# Camera_IR.net
KiCad netlist of a schematic drawn in EasyEDA
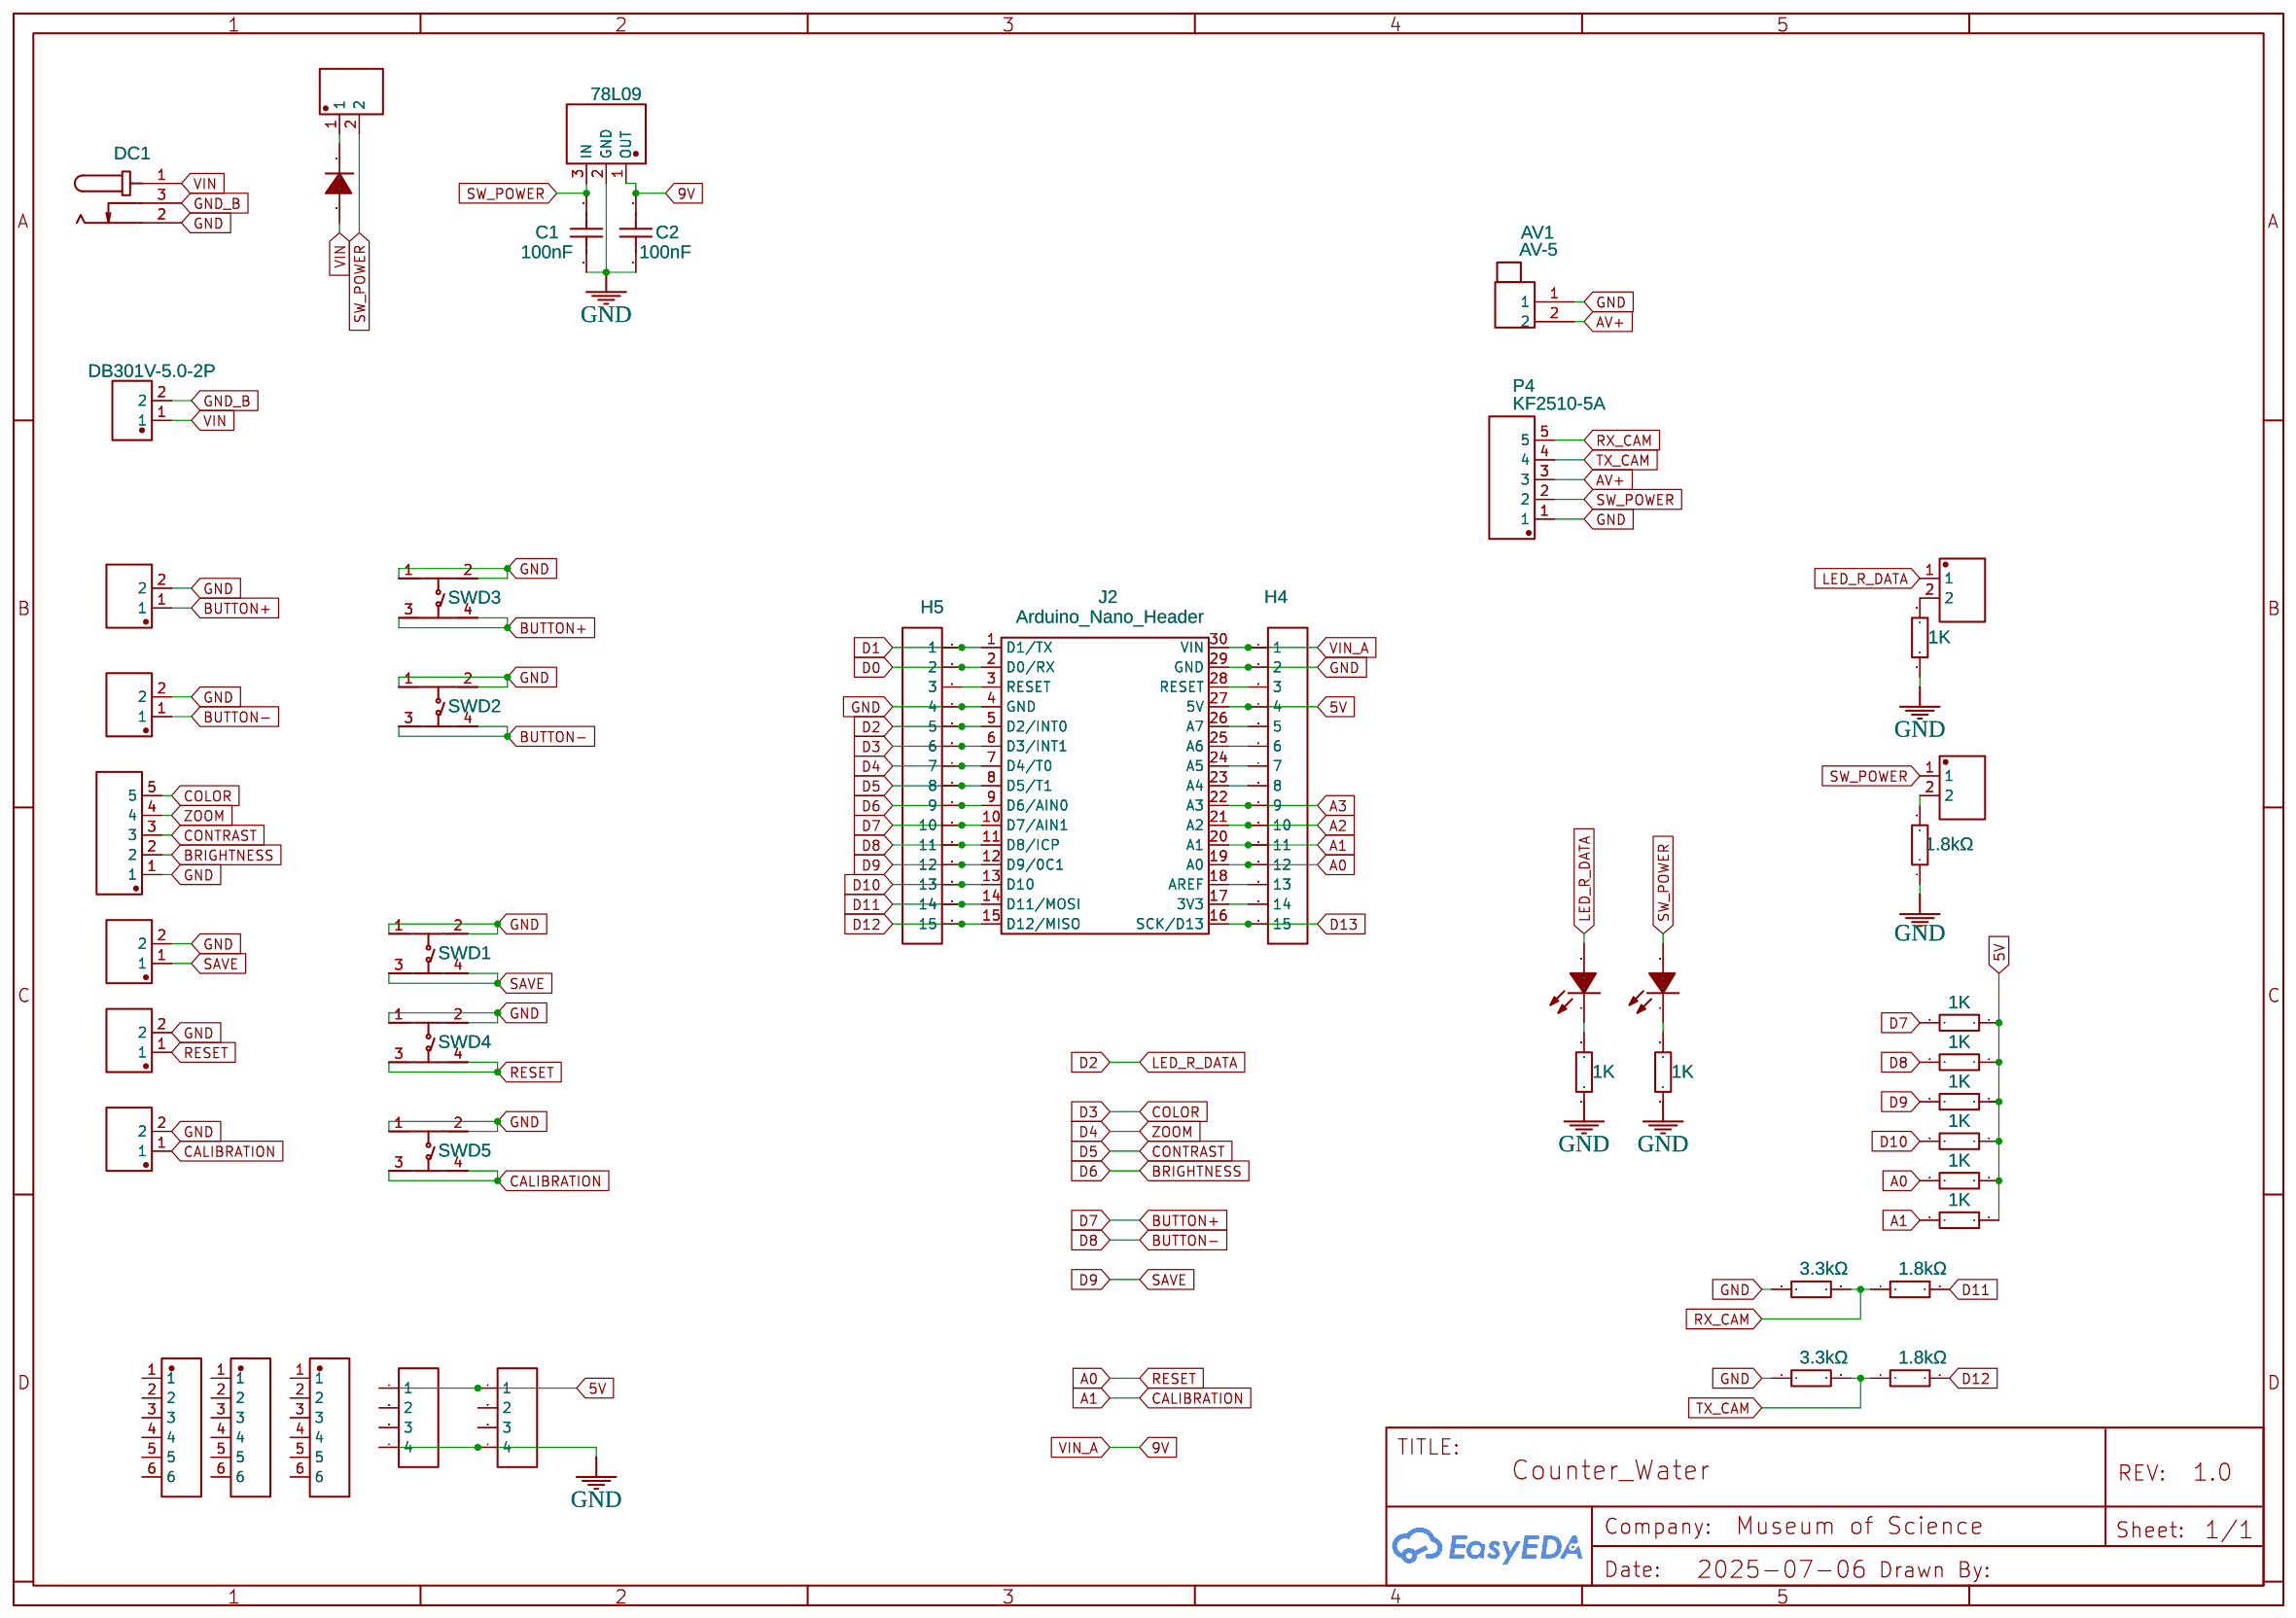
[diagram p0: schematic sheet]

(export (version "E")
  (design (tool "Eeschema 10.0.6"))
  (components
    (comp (ref "A0")
      (value "RESET")
      (fields (field (name "Manufacturer Part") "KF2510-2A") (field (name "Manufacturer") "BOOMELE"))
      (libsource (lib "") (part "KF2510-2A_3"))
    )
    (comp (ref "A1")
      (value "FFC")
      (fields (field (name "Manufacturer Part") "KF2510-2A") (field (name "Manufacturer") "BOOMELE"))
      (libsource (lib "") (part "KF2510-2A_3"))
    )
    (comp (ref "AV1")
      (value "AV-5")
      (fields (field (name "Manufacturer") "BOOMELE(博穆精密)"))
      (libsource (lib "") (part "AV-5"))
    )
    (comp (ref "C1")
      (value "100nF")
      (fields
        (field (name "Manufacturer Part") "CC0603KRX7R9BB104")
        (field (name "Manufacturer") "YAGEO(国巨)")
      )
      (libsource (lib "") (part "CC0603KRX7R9BB104"))
    )
    (comp (ref "C2")
      (value "100nF")
      (fields
        (field (name "Manufacturer Part") "CC0603KRX7R9BB104")
        (field (name "Manufacturer") "YAGEO(国巨)")
      )
      (libsource (lib "") (part "CC0603KRX7R9BB104"))
    )
    (comp (ref "D2")
      (value "LED")
      (fields (field (name "Manufacturer Part") "KF2510-2A") (field (name "Manufacturer") "BOOMELE"))
      (libsource (lib "") (part "KF2510-2A_4"))
    )
    (comp (ref "D7")
      (value "B+")
      (fields (field (name "Manufacturer Part") "KF2510-2A") (field (name "Manufacturer") "BOOMELE"))
      (libsource (lib "") (part "KF2510-2A_1"))
    )
    (comp (ref "D8")
      (value "B-")
      (fields (field (name "Manufacturer Part") "KF2510-2A") (field (name "Manufacturer") "BOOMELE"))
      (libsource (lib "") (part "KF2510-2A_1"))
    )
    (comp (ref "D9")
      (value "SAVE")
      (fields (field (name "Manufacturer Part") "KF2510-2A") (field (name "Manufacturer") "BOOMELE"))
      (libsource (lib "") (part "KF2510-2A_1"))
    )
    (comp (ref "DC1")
      (value "DC")
      (fields (field (name "Manufacturer Part") "DC005-2.0MM") (field (name "Manufacturer") "SOFNG"))
      (libsource (lib "") (part "DC005-2.0MM"))
    )
    (comp (ref "DDM2")
      (value "1N4007")
      (fields (field (name "Manufacturer Part") "1N4007F") (field (name "Manufacturer") "SK"))
      (libsource (lib "") (part "1N4007F"))
    )
    (comp (ref "ERL1")
      (value "1K")
      (fields (field (name "Manufacturer Part") "0603WAF1001T5E") (field (name "Manufacturer") "UniOhm"))
      (libsource (lib "") (part "0603WAF1001T5E"))
    )
    (comp (ref "ERL2")
      (value "1K")
      (fields (field (name "Manufacturer Part") "0603WAF1001T5E") (field (name "Manufacturer") "UniOhm"))
      (libsource (lib "") (part "0603WAF1001T5E_1"))
    )
    (comp (ref "ERL3")
      (value "1K")
      (fields (field (name "Manufacturer Part") "0603WAF1001T5E") (field (name "Manufacturer") "UniOhm"))
      (libsource (lib "") (part "0603WAF1001T5E_1"))
    )
    (comp (ref "ERL4")
      (value "1K")
      (fields (field (name "Manufacturer Part") "0603WAF1001T5E") (field (name "Manufacturer") "UniOhm"))
      (libsource (lib "") (part "0603WAF1001T5E"))
    )
    (comp (ref "ERL5")
      (value "1K")
      (fields (field (name "Manufacturer Part") "0603WAF1001T5E") (field (name "Manufacturer") "UniOhm"))
      (libsource (lib "") (part "0603WAF1001T5E"))
    )
    (comp (ref "ERL6")
      (value "1K")
      (fields (field (name "Manufacturer Part") "0603WAF1001T5E") (field (name "Manufacturer") "UniOhm"))
      (libsource (lib "") (part "0603WAF1001T5E_1"))
    )
    (comp (ref "ERL9")
      (value "1K")
      (fields (field (name "Manufacturer Part") "0603WAF1001T5E") (field (name "Manufacturer") "UniOhm"))
      (libsource (lib "") (part "0603WAF1001T5E_1"))
    )
    (comp (ref "ERL11")
      (value "1K")
      (fields (field (name "Manufacturer Part") "0603WAF1001T5E") (field (name "Manufacturer") "UniOhm"))
      (libsource (lib "") (part "0603WAF1001T5E_1"))
    )
    (comp (ref "ERL12")
      (value "1K")
      (fields (field (name "Manufacturer Part") "0603WAF1001T5E") (field (name "Manufacturer") "UniOhm"))
      (libsource (lib "") (part "0603WAF1001T5E_1"))
    )
    (comp (ref "H4") (value "HDR-F-2.54_1x15") (libsource (lib "") (part "HDR-F-2.54_1x15")))
    (comp (ref "H5") (value "HDR-F-2.54_1x15") (libsource (lib "") (part "HDR-F-2.54_1x15_1")))
    (comp (ref "J2") (value "Arduino_Nano_Header") (libsource (lib "") (part "Arduino_Nano_Header")))
    (comp (ref "J6") (value "HDR-M-2.54_1x4") (libsource (lib "") (part "HDR-M-2.54_1x4")))
    (comp (ref "J7") (value "HDR-M-2.54_1x4") (libsource (lib "") (part "HDR-M-2.54_1x4")))
    (comp (ref "LED4")
      (value "KT-0603R")
      (fields (field (name "Manufacturer") "KENTO"))
      (libsource (lib "") (part "KT-0603R"))
    )
    (comp (ref "LED5")
      (value "KT-0603R")
      (fields (field (name "Manufacturer") "KENTO"))
      (libsource (lib "") (part "KT-0603R"))
    )
    (comp (ref "LED_P")
      (value "LED_POWER")
      (fields (field (name "Manufacturer Part") "KF2510-2A") (field (name "Manufacturer") "BOOMELE"))
      (libsource (lib "") (part "KF2510-2A_2"))
    )
    (comp (ref "P1")
      (value "KF2510-5A")
      (fields (field (name "Manufacturer Part") "2510-5A") (field (name "Manufacturer") "BOOMELE(博穆精密)"))
      (libsource (lib "") (part "KF2510-5A"))
    )
    (comp (ref "P2")
      (value "H6")
      (fields (field (name "Manufacturer Part") "2.54-1*6P母") (field (name "Manufacturer") "BOOMELE(博穆精密)"))
      (libsource (lib "") (part "Header-Female-2.54_1x6"))
    )
    (comp (ref "P3")
      (value "H6")
      (fields (field (name "Manufacturer Part") "2.54-1*6P母") (field (name "Manufacturer") "BOOMELE(博穆精密)"))
      (libsource (lib "") (part "Header-Female-2.54_1x6"))
    )
    (comp (ref "P4")
      (value "KF2510-5A")
      (fields (field (name "Manufacturer Part") "2510-5A") (field (name "Manufacturer") "BOOMELE(博穆精密)"))
      (libsource (lib "") (part "KF2510-5A"))
    )
    (comp (ref "P5")
      (value "H6")
      (fields (field (name "Manufacturer Part") "2.54-1*6P母") (field (name "Manufacturer") "BOOMELE(博穆精密)"))
      (libsource (lib "") (part "Header-Female-2.54_1x6"))
    )
    (comp (ref "R1")
      (value "1.8kΩ")
      (fields
        (field (name "Manufacturer Part") "0603WAF1801T5E")
        (field (name "Manufacturer") "UNI-ROYAL(厚声)")
      )
      (libsource (lib "") (part "0603WAF1801T5E"))
    )
    (comp (ref "R2")
      (value "1.8kΩ")
      (fields
        (field (name "Manufacturer Part") "0603WAF1801T5E")
        (field (name "Manufacturer") "UNI-ROYAL(厚声)")
      )
      (libsource (lib "") (part "0603WAF1801T5E"))
    )
    (comp (ref "R3")
      (value "3.3kΩ")
      (fields
        (field (name "Manufacturer Part") "0402WGF3301TCE")
        (field (name "Manufacturer") "UNI-ROYAL(厚声)")
      )
      (libsource (lib "") (part "0402WGF3301TCE"))
    )
    (comp (ref "R4")
      (value "3.3kΩ")
      (fields
        (field (name "Manufacturer Part") "0402WGF3301TCE")
        (field (name "Manufacturer") "UNI-ROYAL(厚声)")
      )
      (libsource (lib "") (part "0402WGF3301TCE"))
    )
    (comp (ref "R5")
      (value "1.8kΩ")
      (fields
        (field (name "Manufacturer Part") "0603WAF1801T5E")
        (field (name "Manufacturer") "UNI-ROYAL(厚声)")
      )
      (libsource (lib "") (part "0603WAF1801T5E_1"))
    )
    (comp (ref "SWD1")
      (value "TC-6610-7-160G")
      (fields (field (name "Manufacturer") "HCTL(华灿天禄)"))
      (libsource (lib "") (part "TC-6610-7-160G"))
    )
    (comp (ref "SWD2")
      (value "TC-6610-7-160G")
      (fields (field (name "Manufacturer") "HCTL(华灿天禄)"))
      (libsource (lib "") (part "TC-6610-7-160G"))
    )
    (comp (ref "SWD3")
      (value "TC-6610-7-160G")
      (fields (field (name "Manufacturer") "HCTL(华灿天禄)"))
      (libsource (lib "") (part "TC-6610-7-160G"))
    )
    (comp (ref "SWD4")
      (value "TC-6610-7-160G")
      (fields (field (name "Manufacturer") "HCTL(华灿天禄)"))
      (libsource (lib "") (part "TC-6610-7-160G"))
    )
    (comp (ref "SWD5")
      (value "TC-6610-7-160G")
      (fields (field (name "Manufacturer") "HCTL(华灿天禄)"))
      (libsource (lib "") (part "TC-6610-7-160G"))
    )
    (comp (ref "SW_P")
      (value "SW_P")
      (fields (field (name "Manufacturer Part") "KF2510-2A") (field (name "Manufacturer") "BOOMELE"))
      (libsource (lib "") (part "KF2510-2A"))
    )
    (comp (ref "U1")
      (value "78L09")
      (fields (field (name "Manufacturer") "CBI(创基)"))
      (libsource (lib "") (part "78L09U 78L09"))
    )
    (comp (ref "U3")
      (value "DB301V-5.0-2P")
      (fields
        (field (name "Manufacturer Part") "DB301V-5.0-2P-BU-S")
        (field (name "Manufacturer") "DORABO(地博电气)")
      )
      (libsource (lib "") (part "DB301V-5.0-2P"))
    )
  )
  (nets
    (net (code "1") (name "5V") (class "Default")
      (node (ref "ERL11") (pin "1") (pinfunction "1_1") (pintype "input"))
      (node (ref "ERL12") (pin "1") (pinfunction "1_1") (pintype "input"))
      (node (ref "ERL2") (pin "1") (pinfunction "1_1") (pintype "input"))
      (node (ref "ERL3") (pin "1") (pinfunction "1_1") (pintype "input"))
      (node (ref "ERL6") (pin "1") (pinfunction "1_1") (pintype "input"))
      (node (ref "ERL9") (pin "1") (pinfunction "1_1") (pintype "input"))
      (node (ref "H4") (pin "4") (pinfunction "4_4") (pintype "unspecified"))
      (node (ref "J2") (pin "27") (pinfunction "5V_27") (pintype "unspecified"))
      (node (ref "J6") (pin "1") (pinfunction "1_1") (pintype "unspecified"))
      (node (ref "J7") (pin "1") (pinfunction "1_1") (pintype "unspecified"))
    )
    (net (code "2") (name "9V") (class "Default")
      (node (ref "C2") (pin "2") (pinfunction "2_2") (pintype "unspecified"))
      (node (ref "H4") (pin "1") (pinfunction "1_1") (pintype "unspecified"))
      (node (ref "J2") (pin "30") (pinfunction "VIN_30") (pintype "unspecified"))
      (node (ref "U1") (pin "1") (pinfunction "OUT_1") (pintype "unspecified"))
    )
    (net (code "3") (name "A0") (class "Default")
      (node (ref "A0") (pin "1") (pinfunction "1_1") (pintype "unspecified"))
      (node (ref "ERL2") (pin "2") (pinfunction "2_2") (pintype "input"))
      (node (ref "H4") (pin "12") (pinfunction "12_12") (pintype "unspecified"))
      (node (ref "J2") (pin "19") (pinfunction "A0_19") (pintype "unspecified"))
      (node (ref "SWD4") (pin "3") (pinfunction "3_3") (pintype "unspecified"))
      (node (ref "SWD4") (pin "4") (pinfunction "4_4") (pintype "unspecified"))
    )
    (net (code "4") (name "A1") (class "Default")
      (node (ref "A1") (pin "1") (pinfunction "1_1") (pintype "unspecified"))
      (node (ref "ERL3") (pin "2") (pinfunction "2_2") (pintype "input"))
      (node (ref "H4") (pin "11") (pinfunction "11_11") (pintype "unspecified"))
      (node (ref "J2") (pin "20") (pinfunction "A1_20") (pintype "unspecified"))
      (node (ref "SWD5") (pin "3") (pinfunction "3_3") (pintype "unspecified"))
      (node (ref "SWD5") (pin "4") (pinfunction "4_4") (pintype "unspecified"))
    )
    (net (code "5") (name "A2") (class "Default")
      (node (ref "H4") (pin "10") (pinfunction "10_10") (pintype "unspecified"))
      (node (ref "J2") (pin "21") (pinfunction "A2_21") (pintype "unspecified"))
    )
    (net (code "6") (name "A3") (class "Default")
      (node (ref "H4") (pin "9") (pinfunction "9_9") (pintype "unspecified"))
      (node (ref "J2") (pin "22") (pinfunction "A3_22") (pintype "unspecified"))
    )
    (net (code "7") (name "AV+") (class "Default")
      (node (ref "AV1") (pin "2") (pinfunction "2_2") (pintype "unspecified"))
      (node (ref "P4") (pin "3") (pinfunction "3_3") (pintype "unspecified"))
    )
    (net (code "8") (name "BRIGHTNESS") (class "Default")
      (node (ref "H5") (pin "9") (pinfunction "9_9") (pintype "unspecified"))
      (node (ref "J2") (pin "9") (pinfunction "D6/AIN0_9") (pintype "unspecified"))
      (node (ref "P1") (pin "2") (pinfunction "2_2") (pintype "unspecified"))
    )
    (net (code "9") (name "BUTTON+") (class "Default")
      (node (ref "D7") (pin "1") (pinfunction "1_1") (pintype "unspecified"))
      (node (ref "ERL6") (pin "2") (pinfunction "2_2") (pintype "input"))
      (node (ref "H5") (pin "10") (pinfunction "10_10") (pintype "unspecified"))
      (node (ref "J2") (pin "10") (pinfunction "D7/AIN1_10") (pintype "unspecified"))
      (node (ref "SWD3") (pin "3") (pinfunction "3_3") (pintype "unspecified"))
      (node (ref "SWD3") (pin "4") (pinfunction "4_4") (pintype "unspecified"))
    )
    (net (code "10") (name "BUTTON-") (class "Default")
      (node (ref "D8") (pin "1") (pinfunction "1_1") (pintype "unspecified"))
      (node (ref "ERL11") (pin "2") (pinfunction "2_2") (pintype "input"))
      (node (ref "H5") (pin "11") (pinfunction "11_11") (pintype "unspecified"))
      (node (ref "J2") (pin "11") (pinfunction "D8/ICP_11") (pintype "unspecified"))
      (node (ref "SWD2") (pin "3") (pinfunction "3_3") (pintype "unspecified"))
      (node (ref "SWD2") (pin "4") (pinfunction "4_4") (pintype "unspecified"))
    )
    (net (code "11") (name "COLOR") (class "Default")
      (node (ref "H5") (pin "6") (pinfunction "6_6") (pintype "unspecified"))
      (node (ref "J2") (pin "6") (pinfunction "D3/INT1_6") (pintype "unspecified"))
      (node (ref "P1") (pin "5") (pinfunction "5_5") (pintype "unspecified"))
    )
    (net (code "12") (name "CONTRAST") (class "Default")
      (node (ref "H5") (pin "8") (pinfunction "8_8") (pintype "unspecified"))
      (node (ref "J2") (pin "8") (pinfunction "D5/T1_8") (pintype "unspecified"))
      (node (ref "P1") (pin "3") (pinfunction "3_3") (pintype "unspecified"))
    )
    (net (code "13") (name "D0") (class "Default")
      (node (ref "H5") (pin "2") (pinfunction "2_2") (pintype "unspecified"))
      (node (ref "J2") (pin "2") (pinfunction "D0/RX_2") (pintype "unspecified"))
    )
    (net (code "14") (name "D1") (class "Default")
      (node (ref "H5") (pin "1") (pinfunction "1_1") (pintype "unspecified"))
      (node (ref "J2") (pin "1") (pinfunction "D1/TX_1") (pintype "unspecified"))
    )
    (net (code "15") (name "D2") (class "Default")
      (node (ref "D2") (pin "1") (pinfunction "1_1") (pintype "unspecified"))
      (node (ref "H5") (pin "5") (pinfunction "5_5") (pintype "unspecified"))
      (node (ref "J2") (pin "5") (pinfunction "D2/INT0_5") (pintype "unspecified"))
      (node (ref "LED5") (pin "2") (pinfunction "A_2") (pintype "unspecified"))
    )
    (net (code "16") (name "D4") (class "Default")
      (node (ref "H5") (pin "7") (pinfunction "7_7") (pintype "unspecified"))
      (node (ref "J2") (pin "7") (pinfunction "D4/T0_7") (pintype "unspecified"))
      (node (ref "P1") (pin "4") (pinfunction "4_4") (pintype "unspecified"))
    )
    (net (code "17") (name "D9") (class "Default")
      (node (ref "D9") (pin "1") (pinfunction "1_1") (pintype "unspecified"))
      (node (ref "ERL9") (pin "2") (pinfunction "2_2") (pintype "input"))
      (node (ref "H5") (pin "12") (pinfunction "12_12") (pintype "unspecified"))
      (node (ref "J2") (pin "12") (pinfunction "D9/0C1_12") (pintype "unspecified"))
      (node (ref "SWD1") (pin "3") (pinfunction "3_3") (pintype "unspecified"))
      (node (ref "SWD1") (pin "4") (pinfunction "4_4") (pintype "unspecified"))
    )
    (net (code "18") (name "D10") (class "Default")
      (node (ref "ERL12") (pin "2") (pinfunction "2_2") (pintype "input"))
      (node (ref "H5") (pin "13") (pinfunction "13_13") (pintype "unspecified"))
      (node (ref "J2") (pin "13") (pinfunction "D10_13") (pintype "unspecified"))
    )
    (net (code "19") (name "D11") (class "Default")
      (node (ref "H5") (pin "14") (pinfunction "14_14") (pintype "unspecified"))
      (node (ref "J2") (pin "14") (pinfunction "D11/MOSI_14") (pintype "unspecified"))
      (node (ref "R1") (pin "2") (pinfunction "2_2") (pintype "input"))
    )
    (net (code "20") (name "D12") (class "Default")
      (node (ref "H5") (pin "15") (pinfunction "15_15") (pintype "unspecified"))
      (node (ref "J2") (pin "15") (pinfunction "D12/MISO_15") (pintype "unspecified"))
      (node (ref "R2") (pin "2") (pinfunction "2_2") (pintype "input"))
    )
    (net (code "21") (name "D13") (class "Default")
      (node (ref "H4") (pin "15") (pinfunction "15_15") (pintype "unspecified"))
      (node (ref "J2") (pin "16") (pinfunction "SCK/D13_16") (pintype "unspecified"))
    )
    (net (code "22") (name "GND") (class "Default")
      (node (ref "A0") (pin "2") (pinfunction "2_2") (pintype "unspecified"))
      (node (ref "A1") (pin "2") (pinfunction "2_2") (pintype "unspecified"))
      (node (ref "AV1") (pin "1") (pinfunction "1_1") (pintype "unspecified"))
      (node (ref "C1") (pin "1") (pinfunction "1_1") (pintype "unspecified"))
      (node (ref "C2") (pin "1") (pinfunction "1_1") (pintype "unspecified"))
      (node (ref "D7") (pin "2") (pinfunction "2_2") (pintype "unspecified"))
      (node (ref "D8") (pin "2") (pinfunction "2_2") (pintype "unspecified"))
      (node (ref "D9") (pin "2") (pinfunction "2_2") (pintype "unspecified"))
      (node (ref "DC1") (pin "2") (pinfunction "2_2") (pintype "unspecified"))
      (node (ref "ERL1") (pin "1") (pinfunction "1_1") (pintype "input"))
      (node (ref "ERL4") (pin "1") (pinfunction "1_1") (pintype "input"))
      (node (ref "ERL5") (pin "1") (pinfunction "1_1") (pintype "input"))
      (node (ref "H4") (pin "2") (pinfunction "2_2") (pintype "unspecified"))
      (node (ref "H5") (pin "4") (pinfunction "4_4") (pintype "unspecified"))
      (node (ref "J2") (pin "29") (pinfunction "GND_29") (pintype "unspecified"))
      (node (ref "J2") (pin "4") (pinfunction "GND_4") (pintype "unspecified"))
      (node (ref "J6") (pin "4") (pinfunction "4_4") (pintype "unspecified"))
      (node (ref "J7") (pin "4") (pinfunction "4_4") (pintype "unspecified"))
      (node (ref "P1") (pin "1") (pinfunction "1_1") (pintype "unspecified"))
      (node (ref "P4") (pin "1") (pinfunction "1_1") (pintype "unspecified"))
      (node (ref "R3") (pin "1") (pinfunction "1_1") (pintype "input"))
      (node (ref "R4") (pin "1") (pinfunction "1_1") (pintype "input"))
      (node (ref "R5") (pin "1") (pinfunction "1_1") (pintype "input"))
      (node (ref "SWD1") (pin "1") (pinfunction "1_1") (pintype "unspecified"))
      (node (ref "SWD1") (pin "2") (pinfunction "2_2") (pintype "unspecified"))
      (node (ref "SWD2") (pin "1") (pinfunction "1_1") (pintype "unspecified"))
      (node (ref "SWD2") (pin "2") (pinfunction "2_2") (pintype "unspecified"))
      (node (ref "SWD3") (pin "1") (pinfunction "1_1") (pintype "unspecified"))
      (node (ref "SWD3") (pin "2") (pinfunction "2_2") (pintype "unspecified"))
      (node (ref "SWD4") (pin "1") (pinfunction "1_1") (pintype "unspecified"))
      (node (ref "SWD4") (pin "2") (pinfunction "2_2") (pintype "unspecified"))
      (node (ref "SWD5") (pin "1") (pinfunction "1_1") (pintype "unspecified"))
      (node (ref "SWD5") (pin "2") (pinfunction "2_2") (pintype "unspecified"))
      (node (ref "U1") (pin "2") (pinfunction "GND_2") (pintype "unspecified"))
    )
    (net (code "23") (name "GND_B") (class "Default")
      (node (ref "DC1") (pin "3") (pinfunction "3_3") (pintype "unspecified"))
      (node (ref "U3") (pin "2") (pinfunction "2_2") (pintype "unspecified"))
    )
    (net (code "24") (name "Net-(D2-Pad2)") (class "Default")
      (node (ref "D2") (pin "2") (pinfunction "2_2") (pintype "unspecified"))
      (node (ref "ERL5") (pin "2") (pinfunction "2_2") (pintype "input"))
    )
    (net (code "25") (name "Net-(DDM2-C)") (class "Default")
      (node (ref "DDM2") (pin "1") (pinfunction "C_1") (pintype "unspecified"))
      (node (ref "SW_P") (pin "1") (pinfunction "1_1") (pintype "unspecified"))
    )
    (net (code "26") (name "Net-(H4-Pad3)") (class "Default")
      (node (ref "H4") (pin "3") (pinfunction "3_3") (pintype "unspecified"))
      (node (ref "J2") (pin "28") (pinfunction "RESET_28") (pintype "unspecified"))
    )
    (net (code "27") (name "Net-(H5-Pad3)") (class "Default")
      (node (ref "H5") (pin "3") (pinfunction "3_3") (pintype "unspecified"))
      (node (ref "J2") (pin "3") (pinfunction "RESET_3") (pintype "unspecified"))
    )
    (net (code "28") (name "Net-(J2-3V3)") (class "Default")
      (node (ref "H4") (pin "14") (pinfunction "14_14") (pintype "unspecified"))
      (node (ref "J2") (pin "17") (pinfunction "3V3_17") (pintype "unspecified"))
    )
    (net (code "29") (name "Net-(J2-A4)") (class "Default")
      (node (ref "H4") (pin "8") (pinfunction "8_8") (pintype "unspecified"))
      (node (ref "J2") (pin "23") (pinfunction "A4_23") (pintype "unspecified"))
    )
    (net (code "30") (name "Net-(J2-A5)") (class "Default")
      (node (ref "H4") (pin "7") (pinfunction "7_7") (pintype "unspecified"))
      (node (ref "J2") (pin "24") (pinfunction "A5_24") (pintype "unspecified"))
    )
    (net (code "31") (name "Net-(J2-A6)") (class "Default")
      (node (ref "H4") (pin "6") (pinfunction "6_6") (pintype "unspecified"))
      (node (ref "J2") (pin "25") (pinfunction "A6_25") (pintype "unspecified"))
    )
    (net (code "32") (name "Net-(J2-A7)") (class "Default")
      (node (ref "H4") (pin "5") (pinfunction "5_5") (pintype "unspecified"))
      (node (ref "J2") (pin "26") (pinfunction "A7_26") (pintype "unspecified"))
    )
    (net (code "33") (name "Net-(J2-AREF)") (class "Default")
      (node (ref "H4") (pin "13") (pinfunction "13_13") (pintype "unspecified"))
      (node (ref "J2") (pin "18") (pinfunction "AREF_18") (pintype "unspecified"))
    )
    (net (code "34") (name "Net-(LED4-K)") (class "Default")
      (node (ref "ERL4") (pin "2") (pinfunction "2_2") (pintype "input"))
      (node (ref "LED4") (pin "1") (pinfunction "K_1") (pintype "unspecified"))
    )
    (net (code "35") (name "Net-(LED5-K)") (class "Default")
      (node (ref "ERL1") (pin "2") (pinfunction "2_2") (pintype "input"))
      (node (ref "LED5") (pin "1") (pinfunction "K_1") (pintype "unspecified"))
    )
    (net (code "36") (name "Net-(LED_P-Pad2)") (class "Default")
      (node (ref "LED_P") (pin "2") (pinfunction "2_2") (pintype "unspecified"))
      (node (ref "R5") (pin "2") (pinfunction "2_2") (pintype "input"))
    )
    (net (code "37") (name "RX_CAM") (class "Default")
      (node (ref "P4") (pin "5") (pinfunction "5_5") (pintype "unspecified"))
      (node (ref "R1") (pin "1") (pinfunction "1_1") (pintype "input"))
      (node (ref "R3") (pin "2") (pinfunction "2_2") (pintype "input"))
    )
    (net (code "38") (name "SW_POWER") (class "Default")
      (node (ref "C1") (pin "2") (pinfunction "2_2") (pintype "unspecified"))
      (node (ref "LED4") (pin "2") (pinfunction "A_2") (pintype "unspecified"))
      (node (ref "LED_P") (pin "1") (pinfunction "1_1") (pintype "unspecified"))
      (node (ref "P4") (pin "2") (pinfunction "2_2") (pintype "unspecified"))
      (node (ref "SW_P") (pin "2") (pinfunction "2_2") (pintype "unspecified"))
      (node (ref "U1") (pin "3") (pinfunction "IN_3") (pintype "unspecified"))
    )
    (net (code "39") (name "TX_CAM") (class "Default")
      (node (ref "P4") (pin "4") (pinfunction "4_4") (pintype "unspecified"))
      (node (ref "R2") (pin "1") (pinfunction "1_1") (pintype "input"))
      (node (ref "R4") (pin "2") (pinfunction "2_2") (pintype "input"))
    )
    (net (code "40") (name "VIN") (class "Default")
      (node (ref "DC1") (pin "1") (pinfunction "1_1") (pintype "unspecified"))
      (node (ref "DDM2") (pin "2") (pinfunction "A_2") (pintype "unspecified"))
      (node (ref "U3") (pin "1") (pinfunction "1_1") (pintype "unspecified"))
    )
    (net (code "41") (name "unconnected-(J6-Pad2)") (class "Default")
      (node (ref "J6") (pin "2") (pinfunction "2_2") (pintype "unspecified"))
    )
    (net (code "42") (name "unconnected-(J6-Pad3)") (class "Default")
      (node (ref "J6") (pin "3") (pinfunction "3_3") (pintype "unspecified"))
    )
    (net (code "43") (name "unconnected-(J7-Pad2)") (class "Default")
      (node (ref "J7") (pin "2") (pinfunction "2_2") (pintype "unspecified"))
    )
    (net (code "44") (name "unconnected-(J7-Pad3)") (class "Default")
      (node (ref "J7") (pin "3") (pinfunction "3_3") (pintype "unspecified"))
    )
    (net (code "45") (name "unconnected-(P2-Pad1)") (class "Default")
      (node (ref "P2") (pin "1") (pinfunction "1_1") (pintype "unspecified"))
    )
    (net (code "46") (name "unconnected-(P2-Pad2)") (class "Default")
      (node (ref "P2") (pin "2") (pinfunction "2_2") (pintype "unspecified"))
    )
    (net (code "47") (name "unconnected-(P2-Pad3)") (class "Default")
      (node (ref "P2") (pin "3") (pinfunction "3_3") (pintype "unspecified"))
    )
    (net (code "48") (name "unconnected-(P2-Pad4)") (class "Default")
      (node (ref "P2") (pin "4") (pinfunction "4_4") (pintype "unspecified"))
    )
    (net (code "49") (name "unconnected-(P2-Pad5)") (class "Default")
      (node (ref "P2") (pin "5") (pinfunction "5_5") (pintype "unspecified"))
    )
    (net (code "50") (name "unconnected-(P2-Pad6)") (class "Default")
      (node (ref "P2") (pin "6") (pinfunction "6_6") (pintype "unspecified"))
    )
    (net (code "51") (name "unconnected-(P3-Pad1)") (class "Default")
      (node (ref "P3") (pin "1") (pinfunction "1_1") (pintype "unspecified"))
    )
    (net (code "52") (name "unconnected-(P3-Pad2)") (class "Default")
      (node (ref "P3") (pin "2") (pinfunction "2_2") (pintype "unspecified"))
    )
    (net (code "53") (name "unconnected-(P3-Pad3)") (class "Default")
      (node (ref "P3") (pin "3") (pinfunction "3_3") (pintype "unspecified"))
    )
    (net (code "54") (name "unconnected-(P3-Pad4)") (class "Default")
      (node (ref "P3") (pin "4") (pinfunction "4_4") (pintype "unspecified"))
    )
    (net (code "55") (name "unconnected-(P3-Pad5)") (class "Default")
      (node (ref "P3") (pin "5") (pinfunction "5_5") (pintype "unspecified"))
    )
    (net (code "56") (name "unconnected-(P3-Pad6)") (class "Default")
      (node (ref "P3") (pin "6") (pinfunction "6_6") (pintype "unspecified"))
    )
    (net (code "57") (name "unconnected-(P5-Pad1)") (class "Default")
      (node (ref "P5") (pin "1") (pinfunction "1_1") (pintype "unspecified"))
    )
    (net (code "58") (name "unconnected-(P5-Pad2)") (class "Default")
      (node (ref "P5") (pin "2") (pinfunction "2_2") (pintype "unspecified"))
    )
    (net (code "59") (name "unconnected-(P5-Pad3)") (class "Default")
      (node (ref "P5") (pin "3") (pinfunction "3_3") (pintype "unspecified"))
    )
    (net (code "60") (name "unconnected-(P5-Pad4)") (class "Default")
      (node (ref "P5") (pin "4") (pinfunction "4_4") (pintype "unspecified"))
    )
    (net (code "61") (name "unconnected-(P5-Pad5)") (class "Default")
      (node (ref "P5") (pin "5") (pinfunction "5_5") (pintype "unspecified"))
    )
    (net (code "62") (name "unconnected-(P5-Pad6)") (class "Default")
      (node (ref "P5") (pin "6") (pinfunction "6_6") (pintype "unspecified"))
    )
  )
)
